# Bank_A-B-C-D.net
KiCad netlist of a schematic drawn in Altium Designer
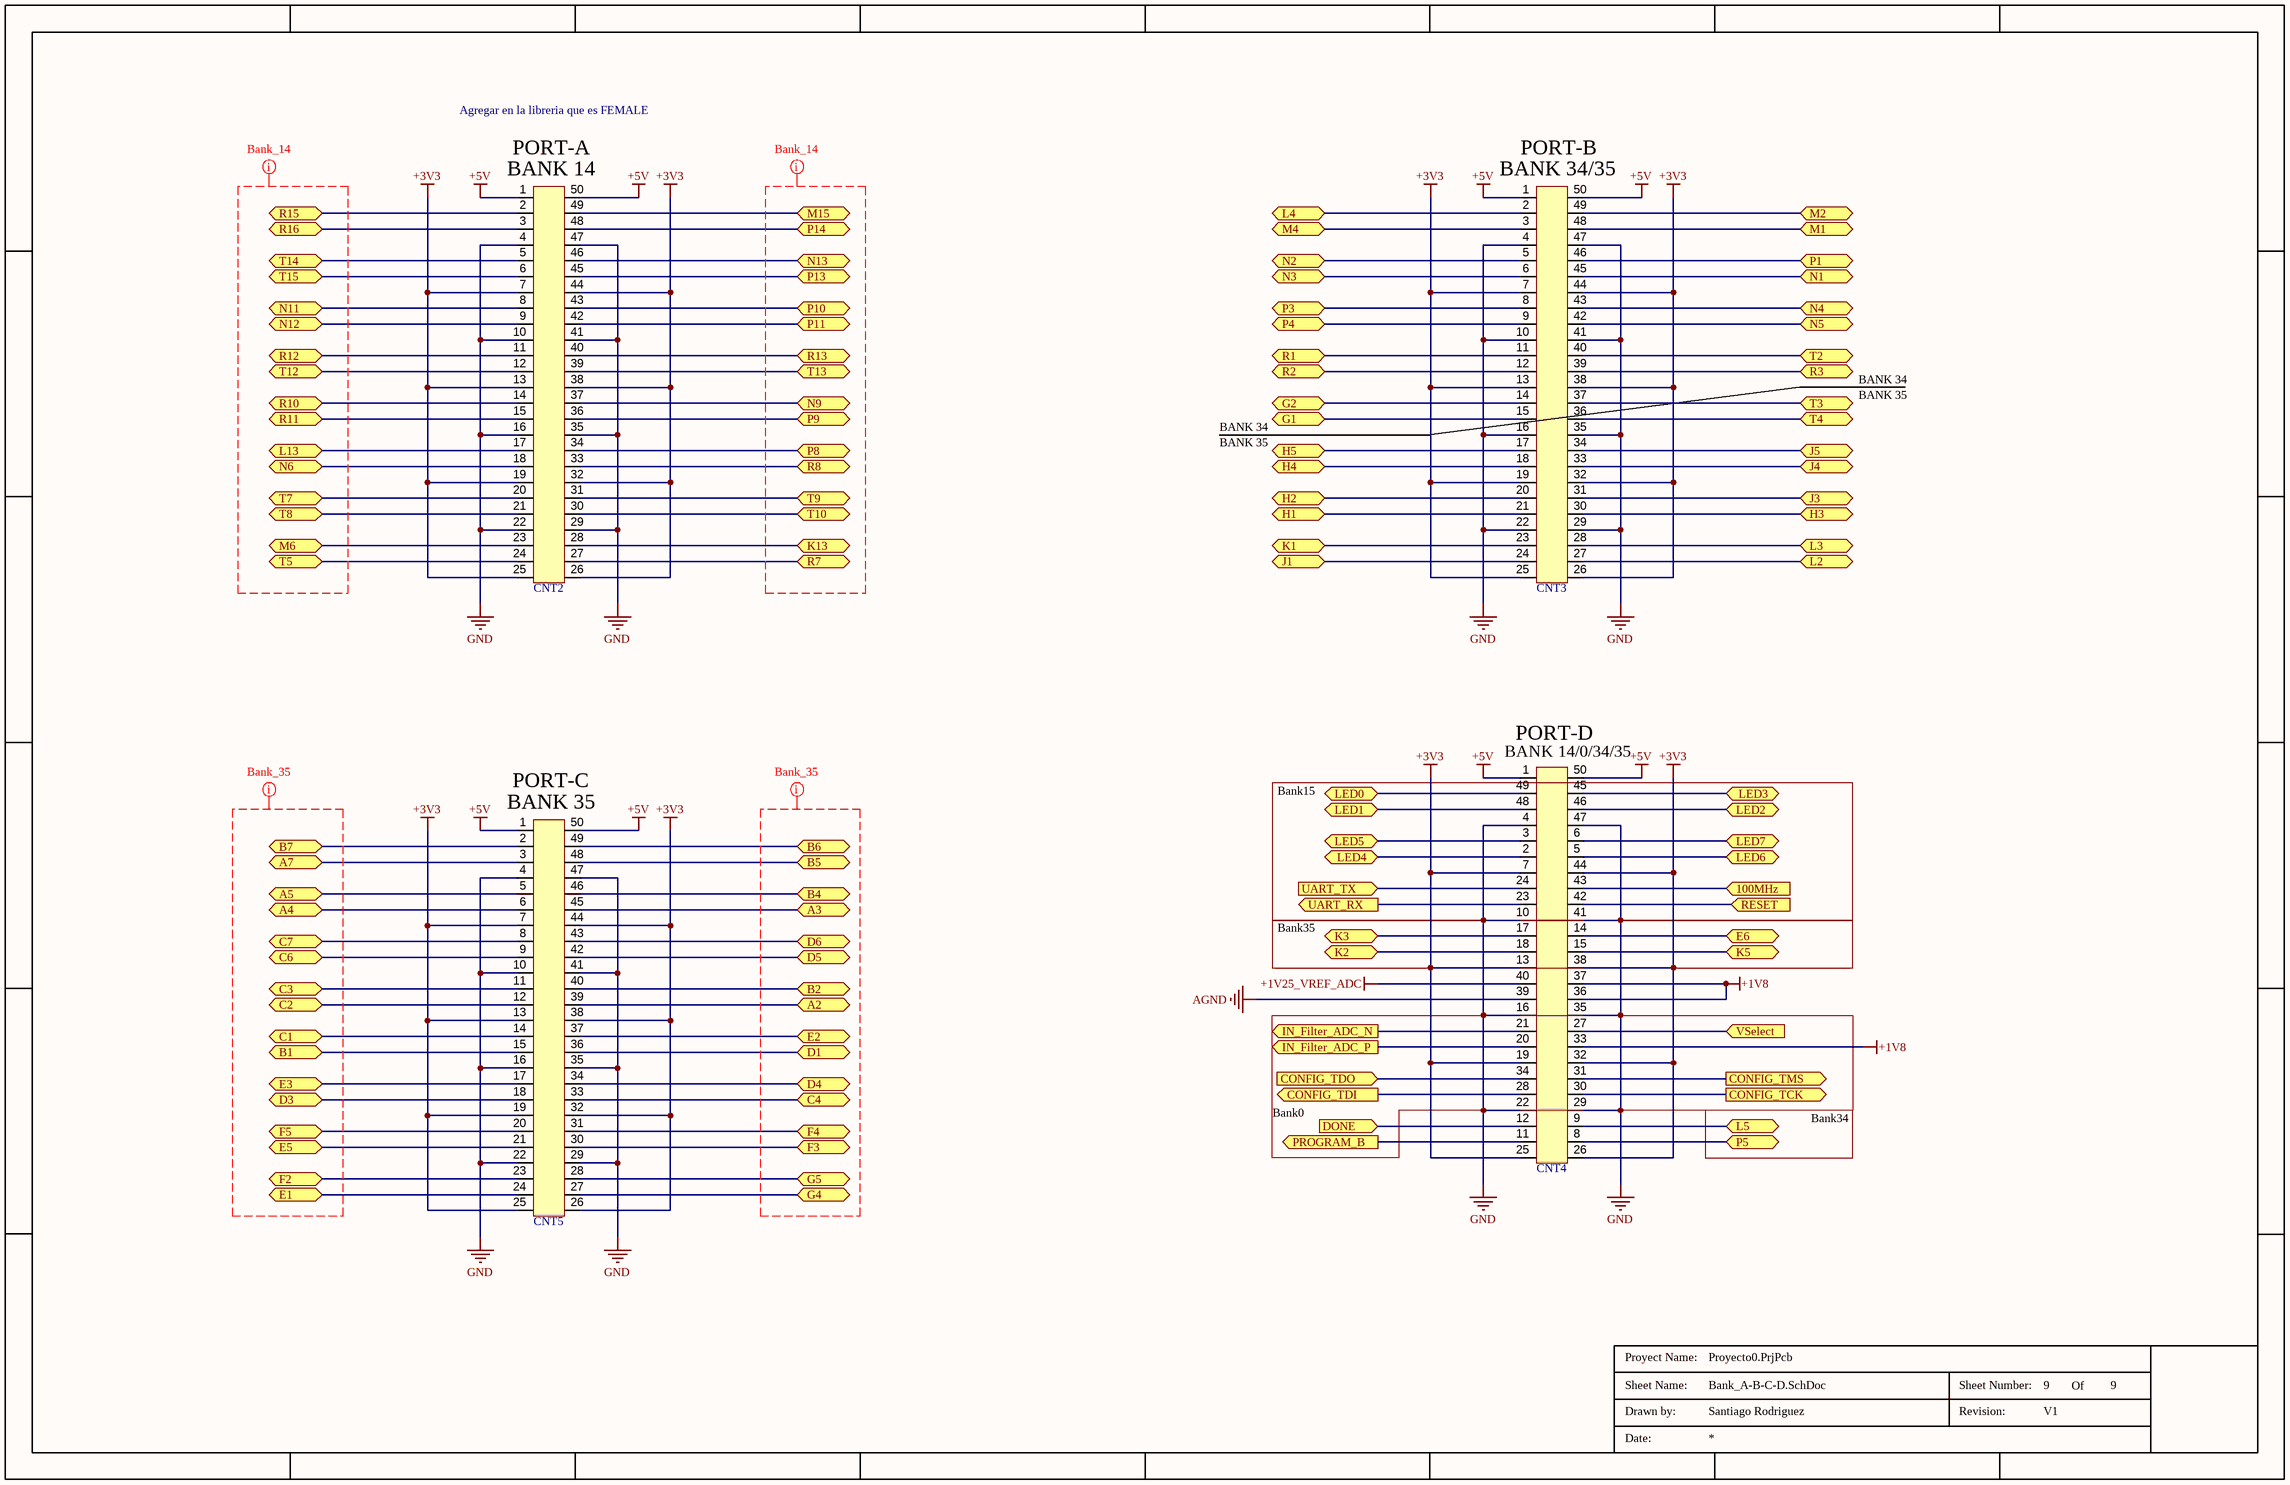
[diagram p0: Bank_A-B-C-D.SchDoc]

(export (version "E")
  (design (tool "Eeschema 10.0.6"))
  (components
    (comp (ref "CNT2")
      (value "528850574")
      (footprint "528850574")
      (description "CONN RCPT 50POS SMD GOLD")
      (fields (field (name "MANUFACTURER") "Molex"))
      (libsource (lib "Connectors") (part "528850574"))
    )
    (comp (ref "CNT3")
      (value "528850574")
      (footprint "528850574")
      (description "CONN RCPT 50POS SMD GOLD")
      (fields (field (name "MANUFACTURER") "Molex"))
      (libsource (lib "Connectors") (part "528850574"))
    )
    (comp (ref "CNT4")
      (value "528850574")
      (footprint "528850574")
      (description "CONN RCPT 50POS SMD GOLD")
      (fields (field (name "MANUFACTURER") "Molex"))
      (libsource (lib "") (part "528850574_1"))
    )
    (comp (ref "CNT5")
      (value "528850574")
      (footprint "528850574")
      (description "CONN RCPT 50POS SMD GOLD")
      (fields (field (name "MANUFACTURER") "Molex"))
      (libsource (lib "Connectors") (part "528850574"))
    )
  )
  (nets
    (net (code "1") (name "+1V8") (class "Default")
      (node (ref "CNT4") (pin "33") (pinfunction "33_33") (pintype "passive"))
      (node (ref "CNT4") (pin "36") (pinfunction "36_36") (pintype "passive"))
      (node (ref "CNT4") (pin "37") (pinfunction "37_37") (pintype "passive"))
    )
    (net (code "2") (name "+1V25_VREF_ADC") (class "Default")
      (node (ref "CNT4") (pin "40") (pinfunction "40_40") (pintype "passive"))
    )
    (net (code "3") (name "+3V3") (class "Default")
      (node (ref "CNT2") (pin "13") (pinfunction "13_13") (pintype "passive"))
      (node (ref "CNT2") (pin "19") (pinfunction "19_19") (pintype "passive"))
      (node (ref "CNT2") (pin "25") (pinfunction "25_25") (pintype "passive"))
      (node (ref "CNT2") (pin "26") (pinfunction "26_26") (pintype "passive"))
      (node (ref "CNT2") (pin "32") (pinfunction "32_32") (pintype "passive"))
      (node (ref "CNT2") (pin "38") (pinfunction "38_38") (pintype "passive"))
      (node (ref "CNT2") (pin "44") (pinfunction "44_44") (pintype "passive"))
      (node (ref "CNT2") (pin "7") (pinfunction "7_7") (pintype "passive"))
      (node (ref "CNT3") (pin "13") (pinfunction "13_13") (pintype "passive"))
      (node (ref "CNT3") (pin "19") (pinfunction "19_19") (pintype "passive"))
      (node (ref "CNT3") (pin "25") (pinfunction "25_25") (pintype "passive"))
      (node (ref "CNT3") (pin "26") (pinfunction "26_26") (pintype "passive"))
      (node (ref "CNT3") (pin "32") (pinfunction "32_32") (pintype "passive"))
      (node (ref "CNT3") (pin "38") (pinfunction "38_38") (pintype "passive"))
      (node (ref "CNT3") (pin "44") (pinfunction "44_44") (pintype "passive"))
      (node (ref "CNT3") (pin "7") (pinfunction "7_7") (pintype "passive"))
      (node (ref "CNT4") (pin "13") (pinfunction "13_13") (pintype "passive"))
      (node (ref "CNT4") (pin "19") (pinfunction "19_19") (pintype "passive"))
      (node (ref "CNT4") (pin "25") (pinfunction "25_25") (pintype "passive"))
      (node (ref "CNT4") (pin "26") (pinfunction "26_26") (pintype "passive"))
      (node (ref "CNT4") (pin "32") (pinfunction "32_32") (pintype "passive"))
      (node (ref "CNT4") (pin "38") (pinfunction "38_38") (pintype "passive"))
      (node (ref "CNT4") (pin "44") (pinfunction "44_44") (pintype "passive"))
      (node (ref "CNT4") (pin "7") (pinfunction "7_7") (pintype "passive"))
      (node (ref "CNT5") (pin "13") (pinfunction "13_13") (pintype "passive"))
      (node (ref "CNT5") (pin "19") (pinfunction "19_19") (pintype "passive"))
      (node (ref "CNT5") (pin "25") (pinfunction "25_25") (pintype "passive"))
      (node (ref "CNT5") (pin "26") (pinfunction "26_26") (pintype "passive"))
      (node (ref "CNT5") (pin "32") (pinfunction "32_32") (pintype "passive"))
      (node (ref "CNT5") (pin "38") (pinfunction "38_38") (pintype "passive"))
      (node (ref "CNT5") (pin "44") (pinfunction "44_44") (pintype "passive"))
      (node (ref "CNT5") (pin "7") (pinfunction "7_7") (pintype "passive"))
    )
    (net (code "4") (name "+5V") (class "Default")
      (node (ref "CNT2") (pin "1") (pintype "passive"))
      (node (ref "CNT2") (pin "50") (pinfunction "50_50") (pintype "passive"))
      (node (ref "CNT3") (pin "1") (pintype "passive"))
      (node (ref "CNT3") (pin "50") (pinfunction "50_50") (pintype "passive"))
      (node (ref "CNT4") (pin "1") (pintype "passive"))
      (node (ref "CNT4") (pin "50") (pinfunction "50_50") (pintype "passive"))
      (node (ref "CNT5") (pin "1") (pintype "passive"))
      (node (ref "CNT5") (pin "50") (pinfunction "50_50") (pintype "passive"))
    )
    (net (code "5") (name "/100MHz") (class "Default")
      (node (ref "CNT4") (pin "43") (pinfunction "43_43") (pintype "passive"))
    )
    (net (code "6") (name "/A2") (class "Default")
      (node (ref "CNT5") (pin "39") (pinfunction "39_39") (pintype "passive"))
    )
    (net (code "7") (name "/A3") (class "Default")
      (node (ref "CNT5") (pin "45") (pinfunction "45_45") (pintype "passive"))
    )
    (net (code "8") (name "/A4") (class "Default")
      (node (ref "CNT5") (pin "6") (pinfunction "6_6") (pintype "passive"))
    )
    (net (code "9") (name "/A5") (class "Default")
      (node (ref "CNT5") (pin "5") (pinfunction "5_5") (pintype "passive"))
    )
    (net (code "10") (name "/A7") (class "Default") (node (ref "CNT5") (pin "3") (pintype "passive")))
    (net (code "11") (name "/B1") (class "Default")
      (node (ref "CNT5") (pin "15") (pinfunction "15_15") (pintype "passive"))
    )
    (net (code "12") (name "/B2") (class "Default")
      (node (ref "CNT5") (pin "40") (pinfunction "40_40") (pintype "passive"))
    )
    (net (code "13") (name "/B4") (class "Default")
      (node (ref "CNT5") (pin "46") (pinfunction "46_46") (pintype "passive"))
    )
    (net (code "14") (name "/B5") (class "Default")
      (node (ref "CNT5") (pin "48") (pinfunction "48_48") (pintype "passive"))
    )
    (net (code "15") (name "/B6") (class "Default")
      (node (ref "CNT5") (pin "49") (pinfunction "49_49") (pintype "passive"))
    )
    (net (code "16") (name "/B7") (class "Default") (node (ref "CNT5") (pin "2") (pintype "passive")))
    (net (code "17") (name "/C1") (class "Default")
      (node (ref "CNT5") (pin "14") (pinfunction "14_14") (pintype "passive"))
    )
    (net (code "18") (name "/C2") (class "Default")
      (node (ref "CNT5") (pin "12") (pinfunction "12_12") (pintype "passive"))
    )
    (net (code "19") (name "/C3") (class "Default")
      (node (ref "CNT5") (pin "11") (pinfunction "11_11") (pintype "passive"))
    )
    (net (code "20") (name "/C4") (class "Default")
      (node (ref "CNT5") (pin "33") (pinfunction "33_33") (pintype "passive"))
    )
    (net (code "21") (name "/C6") (class "Default")
      (node (ref "CNT5") (pin "9") (pinfunction "9_9") (pintype "passive"))
    )
    (net (code "22") (name "/C7") (class "Default")
      (node (ref "CNT5") (pin "8") (pinfunction "8_8") (pintype "passive"))
    )
    (net (code "23") (name "/CONFIG_TCK") (class "Default")
      (node (ref "CNT4") (pin "30") (pinfunction "30_30") (pintype "passive"))
    )
    (net (code "24") (name "/CONFIG_TDI") (class "Default")
      (node (ref "CNT4") (pin "28") (pinfunction "28_28") (pintype "passive"))
    )
    (net (code "25") (name "/CONFIG_TDO") (class "Default")
      (node (ref "CNT4") (pin "34") (pinfunction "34_34") (pintype "passive"))
    )
    (net (code "26") (name "/CONFIG_TMS") (class "Default")
      (node (ref "CNT4") (pin "31") (pinfunction "31_31") (pintype "passive"))
    )
    (net (code "27") (name "/D1") (class "Default")
      (node (ref "CNT5") (pin "36") (pinfunction "36_36") (pintype "passive"))
    )
    (net (code "28") (name "/D3") (class "Default")
      (node (ref "CNT5") (pin "18") (pinfunction "18_18") (pintype "passive"))
    )
    (net (code "29") (name "/D4") (class "Default")
      (node (ref "CNT5") (pin "34") (pinfunction "34_34") (pintype "passive"))
    )
    (net (code "30") (name "/D5") (class "Default")
      (node (ref "CNT5") (pin "42") (pinfunction "42_42") (pintype "passive"))
    )
    (net (code "31") (name "/D6") (class "Default")
      (node (ref "CNT5") (pin "43") (pinfunction "43_43") (pintype "passive"))
    )
    (net (code "32") (name "/DONE") (class "Default")
      (node (ref "CNT4") (pin "12") (pinfunction "12_12") (pintype "passive"))
    )
    (net (code "33") (name "/E1") (class "Default")
      (node (ref "CNT5") (pin "24") (pinfunction "24_24") (pintype "passive"))
    )
    (net (code "34") (name "/E2") (class "Default")
      (node (ref "CNT5") (pin "37") (pinfunction "37_37") (pintype "passive"))
    )
    (net (code "35") (name "/E3") (class "Default")
      (node (ref "CNT5") (pin "17") (pinfunction "17_17") (pintype "passive"))
    )
    (net (code "36") (name "/E5") (class "Default")
      (node (ref "CNT5") (pin "21") (pinfunction "21_21") (pintype "passive"))
    )
    (net (code "37") (name "/E6") (class "Default")
      (node (ref "CNT4") (pin "14") (pinfunction "14_14") (pintype "passive"))
    )
    (net (code "38") (name "/F2") (class "Default")
      (node (ref "CNT5") (pin "23") (pinfunction "23_23") (pintype "passive"))
    )
    (net (code "39") (name "/F3") (class "Default")
      (node (ref "CNT5") (pin "30") (pinfunction "30_30") (pintype "passive"))
    )
    (net (code "40") (name "/F4") (class "Default")
      (node (ref "CNT5") (pin "31") (pinfunction "31_31") (pintype "passive"))
    )
    (net (code "41") (name "/F5") (class "Default")
      (node (ref "CNT5") (pin "20") (pinfunction "20_20") (pintype "passive"))
    )
    (net (code "42") (name "/G1") (class "Default")
      (node (ref "CNT3") (pin "15") (pinfunction "15_15") (pintype "passive"))
    )
    (net (code "43") (name "/G2") (class "Default")
      (node (ref "CNT3") (pin "14") (pinfunction "14_14") (pintype "passive"))
    )
    (net (code "44") (name "/G4") (class "Default")
      (node (ref "CNT5") (pin "27") (pinfunction "27_27") (pintype "passive"))
    )
    (net (code "45") (name "/G5") (class "Default")
      (node (ref "CNT5") (pin "28") (pinfunction "28_28") (pintype "passive"))
    )
    (net (code "46") (name "/H1") (class "Default")
      (node (ref "CNT3") (pin "21") (pinfunction "21_21") (pintype "passive"))
    )
    (net (code "47") (name "/H2") (class "Default")
      (node (ref "CNT3") (pin "20") (pinfunction "20_20") (pintype "passive"))
    )
    (net (code "48") (name "/H3") (class "Default")
      (node (ref "CNT3") (pin "30") (pinfunction "30_30") (pintype "passive"))
    )
    (net (code "49") (name "/H4") (class "Default")
      (node (ref "CNT3") (pin "18") (pinfunction "18_18") (pintype "passive"))
    )
    (net (code "50") (name "/H5") (class "Default")
      (node (ref "CNT3") (pin "17") (pinfunction "17_17") (pintype "passive"))
    )
    (net (code "51") (name "/IN_Filter_ADC_N") (class "Default")
      (node (ref "CNT4") (pin "21") (pinfunction "21_21") (pintype "passive"))
    )
    (net (code "52") (name "/IN_Filter_ADC_P") (class "Default")
      (node (ref "CNT4") (pin "20") (pinfunction "20_20") (pintype "passive"))
    )
    (net (code "53") (name "/J1") (class "Default")
      (node (ref "CNT3") (pin "24") (pinfunction "24_24") (pintype "passive"))
    )
    (net (code "54") (name "/J3") (class "Default")
      (node (ref "CNT3") (pin "31") (pinfunction "31_31") (pintype "passive"))
    )
    (net (code "55") (name "/J4") (class "Default")
      (node (ref "CNT3") (pin "33") (pinfunction "33_33") (pintype "passive"))
    )
    (net (code "56") (name "/J5") (class "Default")
      (node (ref "CNT3") (pin "34") (pinfunction "34_34") (pintype "passive"))
    )
    (net (code "57") (name "/K1") (class "Default")
      (node (ref "CNT3") (pin "23") (pinfunction "23_23") (pintype "passive"))
    )
    (net (code "58") (name "/K2") (class "Default")
      (node (ref "CNT4") (pin "18") (pinfunction "18_18") (pintype "passive"))
    )
    (net (code "59") (name "/K3") (class "Default")
      (node (ref "CNT4") (pin "17") (pinfunction "17_17") (pintype "passive"))
    )
    (net (code "60") (name "/K5") (class "Default")
      (node (ref "CNT4") (pin "15") (pinfunction "15_15") (pintype "passive"))
    )
    (net (code "61") (name "/K13") (class "Default")
      (node (ref "CNT2") (pin "28") (pinfunction "28_28") (pintype "passive"))
    )
    (net (code "62") (name "/L2") (class "Default")
      (node (ref "CNT3") (pin "27") (pinfunction "27_27") (pintype "passive"))
    )
    (net (code "63") (name "/L3") (class "Default")
      (node (ref "CNT3") (pin "28") (pinfunction "28_28") (pintype "passive"))
    )
    (net (code "64") (name "/L4") (class "Default") (node (ref "CNT3") (pin "2") (pintype "passive")))
    (net (code "65") (name "/L5") (class "Default")
      (node (ref "CNT4") (pin "9") (pinfunction "9_9") (pintype "passive"))
    )
    (net (code "66") (name "/L13") (class "Default")
      (node (ref "CNT2") (pin "17") (pinfunction "17_17") (pintype "passive"))
    )
    (net (code "67") (name "/LED0") (class "Default")
      (node (ref "CNT4") (pin "49") (pinfunction "49_49") (pintype "passive"))
    )
    (net (code "68") (name "/LED1") (class "Default")
      (node (ref "CNT4") (pin "48") (pinfunction "48_48") (pintype "passive"))
    )
    (net (code "69") (name "/LED2") (class "Default")
      (node (ref "CNT4") (pin "46") (pinfunction "46_46") (pintype "passive"))
    )
    (net (code "70") (name "/LED3") (class "Default")
      (node (ref "CNT4") (pin "45") (pinfunction "45_45") (pintype "passive"))
    )
    (net (code "71") (name "/LED4") (class "Default") (node (ref "CNT4") (pin "2") (pintype "passive")))
    (net (code "72") (name "/LED5") (class "Default") (node (ref "CNT4") (pin "3") (pintype "passive")))
    (net (code "73") (name "/LED6") (class "Default")
      (node (ref "CNT4") (pin "5") (pinfunction "5_5") (pintype "passive"))
    )
    (net (code "74") (name "/LED7") (class "Default")
      (node (ref "CNT4") (pin "6") (pinfunction "6_6") (pintype "passive"))
    )
    (net (code "75") (name "/M1") (class "Default")
      (node (ref "CNT3") (pin "48") (pinfunction "48_48") (pintype "passive"))
    )
    (net (code "76") (name "/M2") (class "Default")
      (node (ref "CNT3") (pin "49") (pinfunction "49_49") (pintype "passive"))
    )
    (net (code "77") (name "/M4") (class "Default") (node (ref "CNT3") (pin "3") (pintype "passive")))
    (net (code "78") (name "/M6") (class "Default")
      (node (ref "CNT2") (pin "23") (pinfunction "23_23") (pintype "passive"))
    )
    (net (code "79") (name "/M15") (class "Default")
      (node (ref "CNT2") (pin "49") (pinfunction "49_49") (pintype "passive"))
    )
    (net (code "80") (name "/N1") (class "Default")
      (node (ref "CNT3") (pin "45") (pinfunction "45_45") (pintype "passive"))
    )
    (net (code "81") (name "/N2") (class "Default")
      (node (ref "CNT3") (pin "5") (pinfunction "5_5") (pintype "passive"))
    )
    (net (code "82") (name "/N3") (class "Default")
      (node (ref "CNT3") (pin "6") (pinfunction "6_6") (pintype "passive"))
    )
    (net (code "83") (name "/N4") (class "Default")
      (node (ref "CNT3") (pin "43") (pinfunction "43_43") (pintype "passive"))
    )
    (net (code "84") (name "/N5") (class "Default")
      (node (ref "CNT3") (pin "42") (pinfunction "42_42") (pintype "passive"))
    )
    (net (code "85") (name "/N6") (class "Default")
      (node (ref "CNT2") (pin "18") (pinfunction "18_18") (pintype "passive"))
    )
    (net (code "86") (name "/N9") (class "Default")
      (node (ref "CNT2") (pin "37") (pinfunction "37_37") (pintype "passive"))
    )
    (net (code "87") (name "/N11") (class "Default")
      (node (ref "CNT2") (pin "8") (pinfunction "8_8") (pintype "passive"))
    )
    (net (code "88") (name "/N12") (class "Default")
      (node (ref "CNT2") (pin "9") (pinfunction "9_9") (pintype "passive"))
    )
    (net (code "89") (name "/N13") (class "Default")
      (node (ref "CNT2") (pin "46") (pinfunction "46_46") (pintype "passive"))
    )
    (net (code "90") (name "/P1") (class "Default")
      (node (ref "CNT3") (pin "46") (pinfunction "46_46") (pintype "passive"))
    )
    (net (code "91") (name "/P3") (class "Default")
      (node (ref "CNT3") (pin "8") (pinfunction "8_8") (pintype "passive"))
    )
    (net (code "92") (name "/P4") (class "Default")
      (node (ref "CNT3") (pin "9") (pinfunction "9_9") (pintype "passive"))
    )
    (net (code "93") (name "/P5") (class "Default")
      (node (ref "CNT4") (pin "8") (pinfunction "8_8") (pintype "passive"))
    )
    (net (code "94") (name "/P8") (class "Default")
      (node (ref "CNT2") (pin "34") (pinfunction "34_34") (pintype "passive"))
    )
    (net (code "95") (name "/P9") (class "Default")
      (node (ref "CNT2") (pin "36") (pinfunction "36_36") (pintype "passive"))
    )
    (net (code "96") (name "/P10") (class "Default")
      (node (ref "CNT2") (pin "43") (pinfunction "43_43") (pintype "passive"))
    )
    (net (code "97") (name "/P11") (class "Default")
      (node (ref "CNT2") (pin "42") (pinfunction "42_42") (pintype "passive"))
    )
    (net (code "98") (name "/P13") (class "Default")
      (node (ref "CNT2") (pin "45") (pinfunction "45_45") (pintype "passive"))
    )
    (net (code "99") (name "/P14") (class "Default")
      (node (ref "CNT2") (pin "48") (pinfunction "48_48") (pintype "passive"))
    )
    (net (code "100") (name "/PROGRAM_B") (class "Default")
      (node (ref "CNT4") (pin "11") (pinfunction "11_11") (pintype "passive"))
    )
    (net (code "101") (name "/R1") (class "Default")
      (node (ref "CNT3") (pin "11") (pinfunction "11_11") (pintype "passive"))
    )
    (net (code "102") (name "/R2") (class "Default")
      (node (ref "CNT3") (pin "12") (pinfunction "12_12") (pintype "passive"))
    )
    (net (code "103") (name "/R3") (class "Default")
      (node (ref "CNT3") (pin "39") (pinfunction "39_39") (pintype "passive"))
    )
    (net (code "104") (name "/R7") (class "Default")
      (node (ref "CNT2") (pin "27") (pinfunction "27_27") (pintype "passive"))
    )
    (net (code "105") (name "/R8") (class "Default")
      (node (ref "CNT2") (pin "33") (pinfunction "33_33") (pintype "passive"))
    )
    (net (code "106") (name "/R10") (class "Default")
      (node (ref "CNT2") (pin "14") (pinfunction "14_14") (pintype "passive"))
    )
    (net (code "107") (name "/R11") (class "Default")
      (node (ref "CNT2") (pin "15") (pinfunction "15_15") (pintype "passive"))
    )
    (net (code "108") (name "/R12") (class "Default")
      (node (ref "CNT2") (pin "11") (pinfunction "11_11") (pintype "passive"))
    )
    (net (code "109") (name "/R13") (class "Default")
      (node (ref "CNT2") (pin "40") (pinfunction "40_40") (pintype "passive"))
    )
    (net (code "110") (name "/R15") (class "Default") (node (ref "CNT2") (pin "2") (pintype "passive")))
    (net (code "111") (name "/R16") (class "Default") (node (ref "CNT2") (pin "3") (pintype "passive")))
    (net (code "112") (name "/RESET") (class "Default")
      (node (ref "CNT4") (pin "42") (pinfunction "42_42") (pintype "passive"))
    )
    (net (code "113") (name "/T2") (class "Default")
      (node (ref "CNT3") (pin "40") (pinfunction "40_40") (pintype "passive"))
    )
    (net (code "114") (name "/T3") (class "Default")
      (node (ref "CNT3") (pin "37") (pinfunction "37_37") (pintype "passive"))
    )
    (net (code "115") (name "/T4") (class "Default")
      (node (ref "CNT3") (pin "36") (pinfunction "36_36") (pintype "passive"))
    )
    (net (code "116") (name "/T5") (class "Default")
      (node (ref "CNT2") (pin "24") (pinfunction "24_24") (pintype "passive"))
    )
    (net (code "117") (name "/T7") (class "Default")
      (node (ref "CNT2") (pin "20") (pinfunction "20_20") (pintype "passive"))
    )
    (net (code "118") (name "/T8") (class "Default")
      (node (ref "CNT2") (pin "21") (pinfunction "21_21") (pintype "passive"))
    )
    (net (code "119") (name "/T9") (class "Default")
      (node (ref "CNT2") (pin "31") (pinfunction "31_31") (pintype "passive"))
    )
    (net (code "120") (name "/T10") (class "Default")
      (node (ref "CNT2") (pin "30") (pinfunction "30_30") (pintype "passive"))
    )
    (net (code "121") (name "/T12") (class "Default")
      (node (ref "CNT2") (pin "12") (pinfunction "12_12") (pintype "passive"))
    )
    (net (code "122") (name "/T13") (class "Default")
      (node (ref "CNT2") (pin "39") (pinfunction "39_39") (pintype "passive"))
    )
    (net (code "123") (name "/T14") (class "Default")
      (node (ref "CNT2") (pin "5") (pinfunction "5_5") (pintype "passive"))
    )
    (net (code "124") (name "/T15") (class "Default")
      (node (ref "CNT2") (pin "6") (pinfunction "6_6") (pintype "passive"))
    )
    (net (code "125") (name "/UART_RX") (class "Default")
      (node (ref "CNT4") (pin "23") (pinfunction "23_23") (pintype "passive"))
    )
    (net (code "126") (name "/UART_TX") (class "Default")
      (node (ref "CNT4") (pin "24") (pinfunction "24_24") (pintype "passive"))
    )
    (net (code "127") (name "/VSelect") (class "Default")
      (node (ref "CNT4") (pin "27") (pinfunction "27_27") (pintype "passive"))
    )
    (net (code "128") (name "AGND") (class "Default")
      (node (ref "CNT4") (pin "39") (pinfunction "39_39") (pintype "passive"))
    )
    (net (code "129") (name "GND") (class "Default")
      (node (ref "CNT2") (pin "10") (pinfunction "10_10") (pintype "passive"))
      (node (ref "CNT2") (pin "16") (pinfunction "16_16") (pintype "passive"))
      (node (ref "CNT2") (pin "22") (pinfunction "22_22") (pintype "passive"))
      (node (ref "CNT2") (pin "29") (pinfunction "29_29") (pintype "passive"))
      (node (ref "CNT2") (pin "35") (pinfunction "35_35") (pintype "passive"))
      (node (ref "CNT2") (pin "4") (pinfunction "4_4") (pintype "passive"))
      (node (ref "CNT2") (pin "41") (pinfunction "41_41") (pintype "passive"))
      (node (ref "CNT2") (pin "47") (pinfunction "47_47") (pintype "passive"))
      (node (ref "CNT3") (pin "10") (pinfunction "10_10") (pintype "passive"))
      (node (ref "CNT3") (pin "16") (pinfunction "16_16") (pintype "passive"))
      (node (ref "CNT3") (pin "22") (pinfunction "22_22") (pintype "passive"))
      (node (ref "CNT3") (pin "29") (pinfunction "29_29") (pintype "passive"))
      (node (ref "CNT3") (pin "35") (pinfunction "35_35") (pintype "passive"))
      (node (ref "CNT3") (pin "4") (pinfunction "4_4") (pintype "passive"))
      (node (ref "CNT3") (pin "41") (pinfunction "41_41") (pintype "passive"))
      (node (ref "CNT3") (pin "47") (pinfunction "47_47") (pintype "passive"))
      (node (ref "CNT4") (pin "10") (pinfunction "10_10") (pintype "passive"))
      (node (ref "CNT4") (pin "16") (pinfunction "16_16") (pintype "passive"))
      (node (ref "CNT4") (pin "22") (pinfunction "22_22") (pintype "passive"))
      (node (ref "CNT4") (pin "29") (pinfunction "29_29") (pintype "passive"))
      (node (ref "CNT4") (pin "35") (pinfunction "35_35") (pintype "passive"))
      (node (ref "CNT4") (pin "4") (pinfunction "4_4") (pintype "passive"))
      (node (ref "CNT4") (pin "41") (pinfunction "41_41") (pintype "passive"))
      (node (ref "CNT4") (pin "47") (pinfunction "47_47") (pintype "passive"))
      (node (ref "CNT5") (pin "10") (pinfunction "10_10") (pintype "passive"))
      (node (ref "CNT5") (pin "16") (pinfunction "16_16") (pintype "passive"))
      (node (ref "CNT5") (pin "22") (pinfunction "22_22") (pintype "passive"))
      (node (ref "CNT5") (pin "29") (pinfunction "29_29") (pintype "passive"))
      (node (ref "CNT5") (pin "35") (pinfunction "35_35") (pintype "passive"))
      (node (ref "CNT5") (pin "4") (pinfunction "4_4") (pintype "passive"))
      (node (ref "CNT5") (pin "41") (pinfunction "41_41") (pintype "passive"))
      (node (ref "CNT5") (pin "47") (pinfunction "47_47") (pintype "passive"))
    )
  )
)
